# Sheet1.net
KiCad netlist of a schematic drawn in Altium Designer
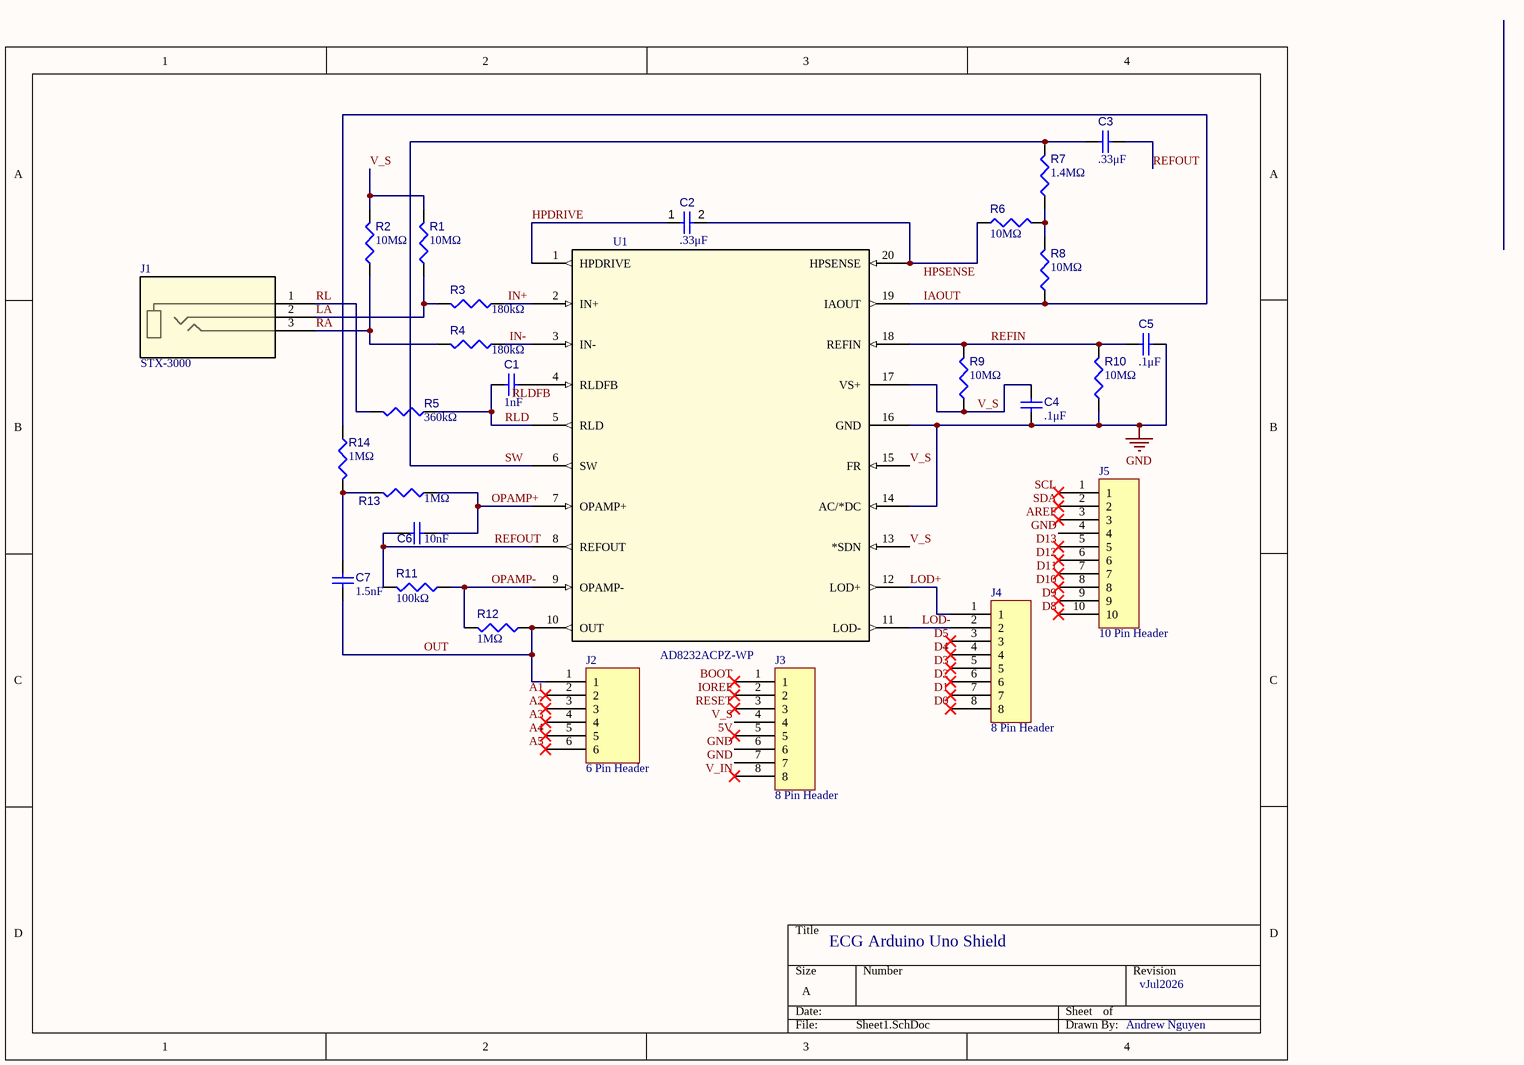
[diagram p0: Sheet1.SchDoc]

(export (version "E")
  (design (tool "Eeschema 10.0.6"))
  (components
    (comp (ref "C1")
      (value "1nF")
      (footprint "CAPC0402(1005)33_L")
      (description "CAP CER 1nF 50V C0G 0402")
      (fields (field (name "TOLERANCE") "10%"))
      (libsource (lib "Andrew Nguyen") (part "CAP-NP-2"))
    )
    (comp (ref "C2")
      (value ".33μF")
      (footprint "CAPC0402(1005)33_L")
      (description "CAP CER 330nF 10V X7R 0402")
      (fields (field (name "TOLERANCE") "10%"))
      (libsource (lib "") (part "CAP-NP-2_1"))
    )
    (comp (ref "C3")
      (value ".33μF")
      (footprint "CAPC0402(1005)33_L")
      (description "CAP CER 330nF 10V X7R 0402")
      (fields (field (name "TOLERANCE") "10%"))
      (libsource (lib "Andrew Nguyen") (part "CAP-NP-2"))
    )
    (comp (ref "C4")
      (value ".1μF")
      (footprint "CAPC0402(1005)33_L")
      (description "CAP CER 100nF 16V X7R 0402")
      (fields (field (name "TOLERANCE") "10%"))
      (libsource (lib "Andrew Nguyen") (part "CAP-NP-2"))
    )
    (comp (ref "C5")
      (value ".1μF")
      (footprint "CAPC0402(1005)33_L")
      (description "CAP CER 100nF 16V X7R 0402")
      (fields (field (name "TOLERANCE") "10%") (field (name "Comment") "Capacitor 1nF +/-20% 50V 0402"))
      (libsource (lib "Andrew Nguyen") (part "CAP-NP-2"))
    )
    (comp (ref "C6")
      (value "10nF")
      (footprint "CAPC0402(1005)33_L")
      (description "CAP CER 10nF 50V X7R 0402")
      (fields (field (name "TOLERANCE") "10%") (field (name "Comment") "Capacitor 1nF +/-20% 50V 0402"))
      (libsource (lib "Andrew Nguyen") (part "CAP-NP-2"))
    )
    (comp (ref "C7")
      (value "1.5nF")
      (footprint "CAPC0402(1005)33_L")
      (description "CAP CER 1.5nF 50V X7R 0402")
      (fields (field (name "TOLERANCE") "10%") (field (name "Comment") "Capacitor 1nF +/-20% 50V 0402"))
      (libsource (lib "Andrew Nguyen") (part "CAP-NP-2"))
    )
    (comp (ref "J1")
      (value "STX-3000")
      (footprint "STX-3000_KYC")
      (fields (field (name "COPYRIGHT") "Copyright (C) 2025 Ultra Librarian. All rights reserved."))
      (libsource (lib "STX-3000") (part "STX-3000"))
    )
    (comp (ref "J2")
      (value "6 Pin Header")
      (footprint "6 Pin Header-Footprint-1")
      (description "1x6 Header")
      (libsource (lib "") (part "New symbol 1_1"))
    )
    (comp (ref "J3")
      (value "8 Pin Header")
      (footprint "8 Pin Header-Footprint-1")
      (description "1x8 Header")
      (libsource (lib "Andrew Nguyen") (part "New symbol 1"))
    )
    (comp (ref "J4")
      (value "8 Pin Header")
      (footprint "8 Pin Header-Footprint-1")
      (description "1x8 Header")
      (libsource (lib "Andrew Nguyen") (part "New symbol 1"))
    )
    (comp (ref "J5")
      (value "10 Pin Header")
      (footprint "10 Pin Header-Footprint-1")
      (description "1x10 Header")
      (libsource (lib "Andrew Nguyen") (part "10 Pin Header-Symbol-1"))
    )
    (comp (ref "R1")
      (value "10MΩ")
      (footprint "RESC0402(1005)_L")
      (description "RES 10MΩ ±1% 62.5mW 0402")
      (fields (field (name "TOLERANCE") "1%") (field (name "POWER") "63mW"))
      (libsource (lib "Andrew Nguyen") (part "RES-2"))
    )
    (comp (ref "R2")
      (value "10MΩ")
      (footprint "RESC0402(1005)_L")
      (description "RES 10MΩ ±1% 62.5mW 0402")
      (fields (field (name "TOLERANCE") "1%") (field (name "POWER") "63mW"))
      (libsource (lib "Andrew Nguyen") (part "RES-2"))
    )
    (comp (ref "R3")
      (value "180kΩ")
      (footprint "RESC0402(1005)_L")
      (description "RES 180kΩ ±1% 62.5mW 0402")
      (fields (field (name "TOLERANCE") "1%") (field (name "POWER") "63mW"))
      (libsource (lib "Andrew Nguyen") (part "RES-2"))
    )
    (comp (ref "R4")
      (value "180kΩ")
      (footprint "RESC0402(1005)_L")
      (description "RES 180kΩ ±1% 62.5mW 0402")
      (fields (field (name "TOLERANCE") "1%") (field (name "POWER") "63mW"))
      (libsource (lib "Andrew Nguyen") (part "RES-2"))
    )
    (comp (ref "R5")
      (value "360kΩ")
      (footprint "RESC0402(1005)_L")
      (description "RES 360kΩ ±1% 62.5mW 0402")
      (fields (field (name "TOLERANCE") "1%") (field (name "POWER") "63mW"))
      (libsource (lib "Andrew Nguyen") (part "RES-2"))
    )
    (comp (ref "R6")
      (value "10MΩ")
      (footprint "RESC0402(1005)_L")
      (description "RES 10MΩ ±1% 62.5mW 0402")
      (fields (field (name "TOLERANCE") "1%") (field (name "POWER") "63mW"))
      (libsource (lib "Andrew Nguyen") (part "RES-2"))
    )
    (comp (ref "R7")
      (value "1.4MΩ")
      (footprint "RESC0402(1005)_L")
      (description "RES 1.4MΩ ±1% 62.5mW 0402")
      (fields (field (name "TOLERANCE") "1%") (field (name "POWER") "63mW"))
      (libsource (lib "Andrew Nguyen") (part "RES-2"))
    )
    (comp (ref "R8")
      (value "10MΩ")
      (footprint "RESC0402(1005)_L")
      (description "RES 10MΩ ±1% 62.5mW 0402")
      (fields (field (name "TOLERANCE") "1%") (field (name "POWER") "63mW"))
      (libsource (lib "Andrew Nguyen") (part "RES-2"))
    )
    (comp (ref "R9")
      (value "10MΩ")
      (footprint "RESC0402(1005)_L")
      (description "RES 10MΩ ±1% 62.5mW 0402")
      (fields (field (name "TOLERANCE") "1%") (field (name "POWER") "63mW"))
      (libsource (lib "Andrew Nguyen") (part "RES-2"))
    )
    (comp (ref "R10")
      (value "10MΩ")
      (footprint "RESC0402(1005)_L")
      (description "RES 10MΩ ±1% 62.5mW 0402")
      (fields (field (name "TOLERANCE") "1%") (field (name "POWER") "63mW"))
      (libsource (lib "Andrew Nguyen") (part "RES-2"))
    )
    (comp (ref "R11")
      (value "100kΩ")
      (footprint "RESC0402(1005)_L")
      (description "RES 100kΩ ±1% 62.5mW 0402")
      (fields (field (name "TOLERANCE") "1%") (field (name "POWER") "63mW"))
      (libsource (lib "Andrew Nguyen") (part "RES-2"))
    )
    (comp (ref "R12")
      (value "1MΩ")
      (footprint "RESC0402(1005)_L")
      (description "RES 1MΩ ±1% 62.5mW 0402")
      (fields (field (name "TOLERANCE") "1%") (field (name "POWER") "63mW"))
      (libsource (lib "Andrew Nguyen") (part "RES-2"))
    )
    (comp (ref "R13")
      (value "1MΩ")
      (footprint "RESC0402(1005)_L")
      (description "RES 1MΩ ±1% 62.5mW 0402")
      (fields (field (name "TOLERANCE") "1%") (field (name "POWER") "63mW"))
      (libsource (lib "Andrew Nguyen") (part "RES-2"))
    )
    (comp (ref "R14")
      (value "1MΩ")
      (footprint "RESC0402(1005)_L")
      (description "RES 1MΩ ±1% 62.5mW 0402")
      (fields (field (name "TOLERANCE") "1%") (field (name "POWER") "63mW"))
      (libsource (lib "Andrew Nguyen") (part "RES-2"))
    )
    (comp (ref "U1")
      (value "AD8232ACPZ-WP")
      (footprint "CP_20_10_ADI")
      (description "Single-Lead, Heart Rate Monitor Front End")
      (fields (field (name "COPYRIGHT") "Copyright (C) 2025 Ultra Librarian. All rights reserved."))
      (libsource (lib "AD8232ACPZ-WP") (part "AD8232ACPZ-WP"))
    )
  )
  (nets
    (net (code "1") (name "/5V") (class "Default")
      (node (ref "J3") (pin "5") (pinfunction "5_5") (pintype "passive+no_connect"))
    )
    (net (code "2") (name "/A1") (class "Default")
      (node (ref "J2") (pin "2") (pinfunction "2_2") (pintype "passive+no_connect"))
    )
    (net (code "3") (name "/A2") (class "Default")
      (node (ref "J2") (pin "3") (pinfunction "3_3") (pintype "passive+no_connect"))
    )
    (net (code "4") (name "/A3") (class "Default")
      (node (ref "J2") (pin "4") (pinfunction "4_4") (pintype "passive+no_connect"))
    )
    (net (code "5") (name "/A4") (class "Default")
      (node (ref "J2") (pin "5") (pinfunction "5_5") (pintype "passive+no_connect"))
    )
    (net (code "6") (name "/A5") (class "Default")
      (node (ref "J2") (pin "6") (pinfunction "6_6") (pintype "passive+no_connect"))
    )
    (net (code "7") (name "/AREF") (class "Default")
      (node (ref "J5") (pin "3") (pinfunction "3_3") (pintype "passive+no_connect"))
    )
    (net (code "8") (name "/BOOT") (class "Default")
      (node (ref "J3") (pin "1") (pinfunction "1_1") (pintype "passive+no_connect"))
    )
    (net (code "9") (name "/D0") (class "Default")
      (node (ref "J4") (pin "8") (pinfunction "8_8") (pintype "passive+no_connect"))
    )
    (net (code "10") (name "/D1") (class "Default")
      (node (ref "J4") (pin "7") (pinfunction "7_7") (pintype "passive+no_connect"))
    )
    (net (code "11") (name "/D2") (class "Default")
      (node (ref "J4") (pin "6") (pinfunction "6_6") (pintype "passive+no_connect"))
    )
    (net (code "12") (name "/D3") (class "Default")
      (node (ref "J4") (pin "5") (pinfunction "5_5") (pintype "passive+no_connect"))
    )
    (net (code "13") (name "/D4") (class "Default")
      (node (ref "J4") (pin "4") (pinfunction "4_4") (pintype "passive+no_connect"))
    )
    (net (code "14") (name "/D5") (class "Default")
      (node (ref "J4") (pin "3") (pinfunction "3_3") (pintype "passive+no_connect"))
    )
    (net (code "15") (name "/D8") (class "Default")
      (node (ref "J5") (pin "10") (pinfunction "10_10") (pintype "passive+no_connect"))
    )
    (net (code "16") (name "/D9") (class "Default")
      (node (ref "J5") (pin "9") (pinfunction "9_9") (pintype "passive+no_connect"))
    )
    (net (code "17") (name "/D10") (class "Default")
      (node (ref "J5") (pin "8") (pinfunction "8_8") (pintype "passive+no_connect"))
    )
    (net (code "18") (name "/D11") (class "Default")
      (node (ref "J5") (pin "7") (pinfunction "7_7") (pintype "passive+no_connect"))
    )
    (net (code "19") (name "/D12") (class "Default")
      (node (ref "J5") (pin "6") (pinfunction "6_6") (pintype "passive+no_connect"))
    )
    (net (code "20") (name "/D13") (class "Default")
      (node (ref "J5") (pin "5") (pinfunction "5_5") (pintype "passive+no_connect"))
    )
    (net (code "21") (name "/HPDRIVE") (class "Default")
      (node (ref "C2") (pin "1") (pinfunction "1_1") (pintype "passive"))
      (node (ref "U1") (pin "1") (pinfunction "HPDRIVE_1") (pintype "output"))
    )
    (net (code "22") (name "/HPSENSE") (class "Default")
      (node (ref "C2") (pin "2") (pinfunction "2_2") (pintype "passive"))
      (node (ref "R6") (pin "1") (pinfunction "1_1") (pintype "passive"))
      (node (ref "U1") (pin "20") (pinfunction "HPSENSE_20") (pintype "input"))
    )
    (net (code "23") (name "/IAOUT") (class "Default")
      (node (ref "R14") (pin "1") (pinfunction "1_1") (pintype "passive"))
      (node (ref "R8") (pin "1") (pinfunction "1_1") (pintype "passive"))
      (node (ref "U1") (pin "19") (pinfunction "IAOUT_19") (pintype "output"))
    )
    (net (code "24") (name "/IN+") (class "Default")
      (node (ref "R3") (pin "1") (pinfunction "1_1") (pintype "passive"))
      (node (ref "U1") (pin "2") (pinfunction "IN+_2") (pintype "input"))
    )
    (net (code "25") (name "/IN-") (class "Default")
      (node (ref "R4") (pin "1") (pinfunction "1_1") (pintype "passive"))
      (node (ref "U1") (pin "3") (pinfunction "IN-_3") (pintype "input"))
    )
    (net (code "26") (name "/IOREF") (class "Default")
      (node (ref "J3") (pin "2") (pinfunction "2_2") (pintype "passive+no_connect"))
    )
    (net (code "27") (name "/LA") (class "Default")
      (node (ref "J1") (pin "2") (pinfunction "2_2") (pintype "passive"))
      (node (ref "R1") (pin "1") (pinfunction "1_1") (pintype "passive"))
      (node (ref "R3") (pin "2") (pinfunction "2_2") (pintype "passive"))
    )
    (net (code "28") (name "/LOD+") (class "Default")
      (node (ref "J4") (pin "1") (pinfunction "1_1") (pintype "passive"))
      (node (ref "U1") (pin "12") (pinfunction "LOD+_12") (pintype "output"))
    )
    (net (code "29") (name "/LOD-") (class "Default")
      (node (ref "J4") (pin "2") (pinfunction "2_2") (pintype "passive"))
      (node (ref "U1") (pin "11") (pinfunction "LOD-_11") (pintype "output"))
    )
    (net (code "30") (name "/OPAMP+") (class "Default")
      (node (ref "C6") (pin "2") (pinfunction "2_2") (pintype "passive"))
      (node (ref "R13") (pin "1") (pinfunction "1_1") (pintype "passive"))
      (node (ref "U1") (pin "7") (pinfunction "OPAMP+_7") (pintype "input"))
    )
    (net (code "31") (name "/OPAMP-") (class "Default")
      (node (ref "R11") (pin "1") (pinfunction "1_1") (pintype "passive"))
      (node (ref "R12") (pin "2") (pinfunction "2_2") (pintype "passive"))
      (node (ref "U1") (pin "9") (pinfunction "OPAMP-_9") (pintype "input"))
    )
    (net (code "32") (name "/OUT") (class "Default")
      (node (ref "C7") (pin "2") (pinfunction "2_2") (pintype "passive"))
      (node (ref "J2") (pin "1") (pinfunction "1_1") (pintype "passive"))
      (node (ref "R12") (pin "1") (pinfunction "1_1") (pintype "passive"))
      (node (ref "U1") (pin "10") (pinfunction "OUT_10") (pintype "output"))
    )
    (net (code "33") (name "/RA") (class "Default")
      (node (ref "J1") (pin "3") (pinfunction "3_3") (pintype "passive"))
      (node (ref "R2") (pin "1") (pinfunction "1_1") (pintype "passive"))
      (node (ref "R4") (pin "2") (pinfunction "2_2") (pintype "passive"))
    )
    (net (code "34") (name "/REFIN") (class "Default")
      (node (ref "C5") (pin "1") (pinfunction "1_1") (pintype "passive"))
      (node (ref "R10") (pin "2") (pinfunction "2_2") (pintype "passive"))
      (node (ref "R9") (pin "2") (pinfunction "2_2") (pintype "passive"))
      (node (ref "U1") (pin "18") (pinfunction "REFIN_18") (pintype "input"))
    )
    (net (code "35") (name "/REFOUT") (class "Default")
      (node (ref "C3") (pin "2") (pinfunction "2_2") (pintype "passive"))
      (node (ref "C6") (pin "1") (pinfunction "1_1") (pintype "passive"))
      (node (ref "R11") (pin "2") (pinfunction "2_2") (pintype "passive"))
      (node (ref "U1") (pin "8") (pinfunction "REFOUT_8") (pintype "output"))
    )
    (net (code "36") (name "/RESET") (class "Default")
      (node (ref "J3") (pin "3") (pinfunction "3_3") (pintype "passive+no_connect"))
    )
    (net (code "37") (name "/RL") (class "Default")
      (node (ref "J1") (pin "1") (pinfunction "1_1") (pintype "passive"))
      (node (ref "R5") (pin "2") (pinfunction "2_2") (pintype "passive"))
    )
    (net (code "38") (name "/RLD") (class "Default")
      (node (ref "C1") (pin "1") (pinfunction "1_1") (pintype "passive"))
      (node (ref "R5") (pin "1") (pinfunction "1_1") (pintype "passive"))
      (node (ref "U1") (pin "5") (pinfunction "RLD_5") (pintype "output"))
    )
    (net (code "39") (name "/RLDFB") (class "Default")
      (node (ref "C1") (pin "2") (pinfunction "2_2") (pintype "passive"))
      (node (ref "U1") (pin "4") (pinfunction "RLDFB_4") (pintype "input"))
    )
    (net (code "40") (name "/SCL") (class "Default")
      (node (ref "J5") (pin "1") (pinfunction "1_1") (pintype "passive+no_connect"))
    )
    (net (code "41") (name "/SDA") (class "Default")
      (node (ref "J5") (pin "2") (pinfunction "2_2") (pintype "passive+no_connect"))
    )
    (net (code "42") (name "/SW") (class "Default")
      (node (ref "C3") (pin "1") (pinfunction "1_1") (pintype "passive"))
      (node (ref "R7") (pin "2") (pinfunction "2_2") (pintype "passive"))
      (node (ref "U1") (pin "6") (pinfunction "SW_6") (pintype "output"))
    )
    (net (code "43") (name "/V_IN") (class "Default")
      (node (ref "J3") (pin "8") (pinfunction "8_8") (pintype "passive+no_connect"))
    )
    (net (code "44") (name "/V_S") (class "Default")
      (node (ref "C4") (pin "1") (pinfunction "1_1") (pintype "passive"))
      (node (ref "J3") (pin "4") (pinfunction "4_4") (pintype "passive"))
      (node (ref "R1") (pin "2") (pinfunction "2_2") (pintype "passive"))
      (node (ref "R2") (pin "2") (pinfunction "2_2") (pintype "passive"))
      (node (ref "R9") (pin "1") (pinfunction "1_1") (pintype "passive"))
      (node (ref "U1") (pin "13") (pinfunction "*SDN_13") (pintype "input"))
      (node (ref "U1") (pin "15") (pinfunction "FR_15") (pintype "input"))
      (node (ref "U1") (pin "17") (pinfunction "VS+_17") (pintype "power_in"))
    )
    (net (code "45") (name "GND") (class "Default")
      (node (ref "C4") (pin "2") (pinfunction "2_2") (pintype "passive"))
      (node (ref "C5") (pin "2") (pinfunction "2_2") (pintype "passive"))
      (node (ref "J3") (pin "6") (pinfunction "6_6") (pintype "passive"))
      (node (ref "J3") (pin "7") (pinfunction "7_7") (pintype "passive"))
      (node (ref "J5") (pin "4") (pinfunction "4_4") (pintype "passive"))
      (node (ref "R10") (pin "1") (pinfunction "1_1") (pintype "passive"))
      (node (ref "U1") (pin "14") (pinfunction "AC/*DC_14") (pintype "input"))
      (node (ref "U1") (pin "16") (pinfunction "GND_16") (pintype "power_in"))
    )
    (net (code "46") (name "Net-(C7-Pad1)") (class "Default")
      (node (ref "C7") (pin "1") (pinfunction "1_1") (pintype "passive"))
      (node (ref "R13") (pin "2") (pinfunction "2_2") (pintype "passive"))
      (node (ref "R14") (pin "2") (pinfunction "2_2") (pintype "passive"))
    )
    (net (code "47") (name "Net-(R6-Pad2)") (class "Default")
      (node (ref "R6") (pin "2") (pinfunction "2_2") (pintype "passive"))
      (node (ref "R7") (pin "1") (pinfunction "1_1") (pintype "passive"))
      (node (ref "R8") (pin "2") (pinfunction "2_2") (pintype "passive"))
    )
  )
)
